# NobleAward_Rhodium.net
KiCad netlist of a schematic drawn in EAGLE
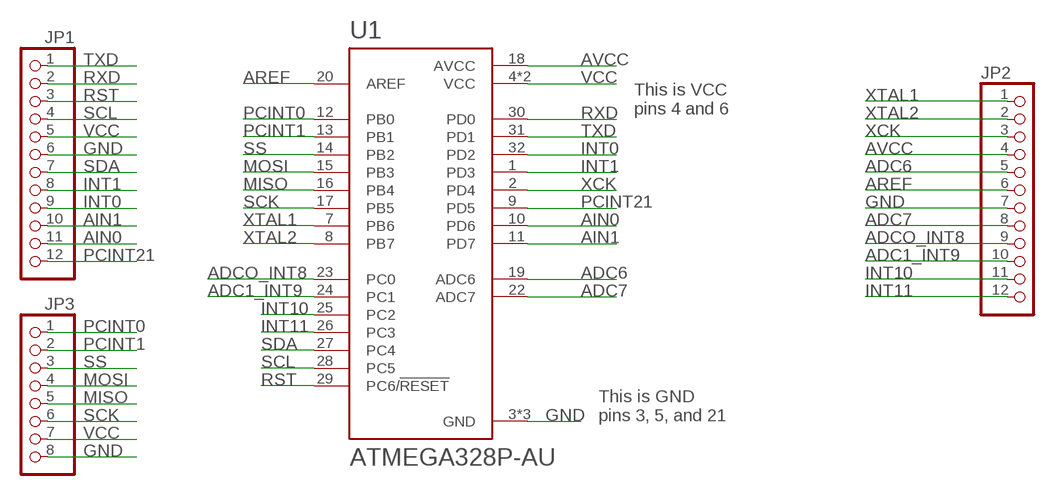
[diagram p0: schematic, sheet 1]

(export (version "E")
  (design (tool "Eeschema 10.0.6"))
  (components
    (comp (ref "JP1")
      (value "PINHD-1X12")
      (footprint "eagle-import:1X12")
      (libsource (lib "eagle-import") (part "PINHD-1X12"))
    )
    (comp (ref "JP2")
      (value "PINHD-1X12")
      (footprint "eagle-import:1X12")
      (libsource (lib "eagle-import") (part "PINHD-1X12"))
    )
    (comp (ref "JP3")
      (value "PINHD-1X8")
      (footprint "eagle-import:1X08")
      (libsource (lib "eagle-import") (part "PINHD-1X8"))
    )
    (comp (ref "U1")
      (value "ATMEGA328P-AU")
      (footprint "eagle-import:QFP80P900X900X120-32N")
      (fields (field (name "MF") "Microchip"))
      (libsource (lib "eagle-import") (part "ATMEGA328P-AU"))
    )
  )
  (nets
    (net (code "1") (name "/ADC1_INT9") (class "Default")
      (node (ref "JP2") (pin "10") (pinfunction "10_10") (pintype "passive"))
      (node (ref "U1") (pin "24") (pinfunction "PC1_24") (pintype "bidirectional"))
    )
    (net (code "2") (name "/ADC6") (class "Default")
      (node (ref "JP2") (pin "5") (pinfunction "5_5") (pintype "passive"))
      (node (ref "U1") (pin "19") (pinfunction "ADC6_19") (pintype "bidirectional"))
    )
    (net (code "3") (name "/ADC7") (class "Default")
      (node (ref "JP2") (pin "8") (pinfunction "8_8") (pintype "passive"))
      (node (ref "U1") (pin "22") (pinfunction "ADC7_22") (pintype "bidirectional"))
    )
    (net (code "4") (name "/ADCO_INT8") (class "Default")
      (node (ref "JP2") (pin "9") (pinfunction "9_9") (pintype "passive"))
      (node (ref "U1") (pin "23") (pinfunction "PC0_23") (pintype "bidirectional"))
    )
    (net (code "5") (name "/AIN0") (class "Default")
      (node (ref "JP1") (pin "11") (pinfunction "11_11") (pintype "passive"))
      (node (ref "U1") (pin "10") (pinfunction "PD6_10") (pintype "bidirectional"))
    )
    (net (code "6") (name "/AIN1") (class "Default")
      (node (ref "JP1") (pin "10") (pinfunction "10_10") (pintype "passive"))
      (node (ref "U1") (pin "11") (pinfunction "PD7_11") (pintype "bidirectional"))
    )
    (net (code "7") (name "/AREF") (class "Default")
      (node (ref "JP2") (pin "6") (pinfunction "6_6") (pintype "passive"))
      (node (ref "U1") (pin "20") (pinfunction "AREF_20") (pintype "input"))
    )
    (net (code "8") (name "/AVCC") (class "Default")
      (node (ref "JP2") (pin "4") (pinfunction "4_4") (pintype "passive"))
      (node (ref "U1") (pin "18") (pinfunction "AVCC_18") (pintype "power_in"))
    )
    (net (code "9") (name "/GND") (class "Default")
      (node (ref "JP1") (pin "6") (pinfunction "6_6") (pintype "passive"))
      (node (ref "JP2") (pin "7") (pinfunction "7_7") (pintype "passive"))
      (node (ref "JP3") (pin "8") (pinfunction "8_8") (pintype "passive"))
      (node (ref "U1") (pin "21") (pinfunction "GND_21") (pintype "power_in"))
      (node (ref "U1") (pin "3") (pinfunction "GND_3") (pintype "power_in"))
      (node (ref "U1") (pin "5") (pinfunction "GND_5") (pintype "power_in"))
    )
    (net (code "10") (name "/INT0") (class "Default")
      (node (ref "JP1") (pin "9") (pinfunction "9_9") (pintype "passive"))
      (node (ref "U1") (pin "32") (pinfunction "PD2_32") (pintype "bidirectional"))
    )
    (net (code "11") (name "/INT1") (class "Default")
      (node (ref "JP1") (pin "8") (pinfunction "8_8") (pintype "passive"))
      (node (ref "U1") (pin "1") (pinfunction "PD3_1") (pintype "bidirectional"))
    )
    (net (code "12") (name "/INT10") (class "Default")
      (node (ref "JP2") (pin "11") (pinfunction "11_11") (pintype "passive"))
      (node (ref "U1") (pin "25") (pinfunction "PC2_25") (pintype "bidirectional"))
    )
    (net (code "13") (name "/INT11") (class "Default")
      (node (ref "JP2") (pin "12") (pinfunction "12_12") (pintype "passive"))
      (node (ref "U1") (pin "26") (pinfunction "PC3_26") (pintype "bidirectional"))
    )
    (net (code "14") (name "/MISO") (class "Default")
      (node (ref "JP3") (pin "5") (pinfunction "5_5") (pintype "passive"))
      (node (ref "U1") (pin "16") (pinfunction "PB4_16") (pintype "bidirectional"))
    )
    (net (code "15") (name "/MOSI") (class "Default")
      (node (ref "JP3") (pin "4") (pinfunction "4_4") (pintype "passive"))
      (node (ref "U1") (pin "15") (pinfunction "PB3_15") (pintype "bidirectional"))
    )
    (net (code "16") (name "/PCINT0") (class "Default")
      (node (ref "JP3") (pin "1") (pinfunction "1_1") (pintype "passive"))
      (node (ref "U1") (pin "12") (pinfunction "PB0_12") (pintype "bidirectional"))
    )
    (net (code "17") (name "/PCINT1") (class "Default")
      (node (ref "JP3") (pin "2") (pinfunction "2_2") (pintype "passive"))
      (node (ref "U1") (pin "13") (pinfunction "PB1_13") (pintype "bidirectional"))
    )
    (net (code "18") (name "/PCINT21") (class "Default")
      (node (ref "JP1") (pin "12") (pinfunction "12_12") (pintype "passive"))
      (node (ref "U1") (pin "9") (pinfunction "PD5_9") (pintype "bidirectional"))
    )
    (net (code "19") (name "/RST") (class "Default")
      (node (ref "JP1") (pin "3") (pinfunction "3_3") (pintype "passive"))
      (node (ref "U1") (pin "29") (pinfunction "PC6/~{RESET}_29") (pintype "bidirectional"))
    )
    (net (code "20") (name "/RXD") (class "Default")
      (node (ref "JP1") (pin "2") (pinfunction "2_2") (pintype "passive"))
      (node (ref "U1") (pin "30") (pinfunction "PD0_30") (pintype "bidirectional"))
    )
    (net (code "21") (name "/SCK") (class "Default")
      (node (ref "JP3") (pin "6") (pinfunction "6_6") (pintype "passive"))
      (node (ref "U1") (pin "17") (pinfunction "PB5_17") (pintype "bidirectional"))
    )
    (net (code "22") (name "/SCL") (class "Default")
      (node (ref "JP1") (pin "4") (pinfunction "4_4") (pintype "passive"))
      (node (ref "U1") (pin "28") (pinfunction "PC5_28") (pintype "bidirectional"))
    )
    (net (code "23") (name "/SDA") (class "Default")
      (node (ref "JP1") (pin "7") (pinfunction "7_7") (pintype "passive"))
      (node (ref "U1") (pin "27") (pinfunction "PC4_27") (pintype "bidirectional"))
    )
    (net (code "24") (name "/SS") (class "Default")
      (node (ref "JP3") (pin "3") (pinfunction "3_3") (pintype "passive"))
      (node (ref "U1") (pin "14") (pinfunction "PB2_14") (pintype "bidirectional"))
    )
    (net (code "25") (name "/TXD") (class "Default")
      (node (ref "JP1") (pin "1") (pinfunction "1_1") (pintype "passive"))
      (node (ref "U1") (pin "31") (pinfunction "PD1_31") (pintype "bidirectional"))
    )
    (net (code "26") (name "/VCC") (class "Default")
      (node (ref "JP1") (pin "5") (pinfunction "5_5") (pintype "passive"))
      (node (ref "JP3") (pin "7") (pinfunction "7_7") (pintype "passive"))
      (node (ref "U1") (pin "4") (pinfunction "VCC_4") (pintype "power_in"))
      (node (ref "U1") (pin "6") (pinfunction "VCC_6") (pintype "power_in"))
    )
    (net (code "27") (name "/XCK") (class "Default")
      (node (ref "JP2") (pin "3") (pinfunction "3_3") (pintype "passive"))
      (node (ref "U1") (pin "2") (pinfunction "PD4_2") (pintype "bidirectional"))
    )
    (net (code "28") (name "/XTAL1") (class "Default")
      (node (ref "JP2") (pin "1") (pinfunction "1_1") (pintype "passive"))
      (node (ref "U1") (pin "7") (pinfunction "PB6_7") (pintype "bidirectional"))
    )
    (net (code "29") (name "/XTAL2") (class "Default")
      (node (ref "JP2") (pin "2") (pinfunction "2_2") (pintype "passive"))
      (node (ref "U1") (pin "8") (pinfunction "PB7_8") (pintype "bidirectional"))
    )
  )
)
